# SCH_Endurance_drone_1.net
KiCad netlist of a schematic drawn in EasyEDA
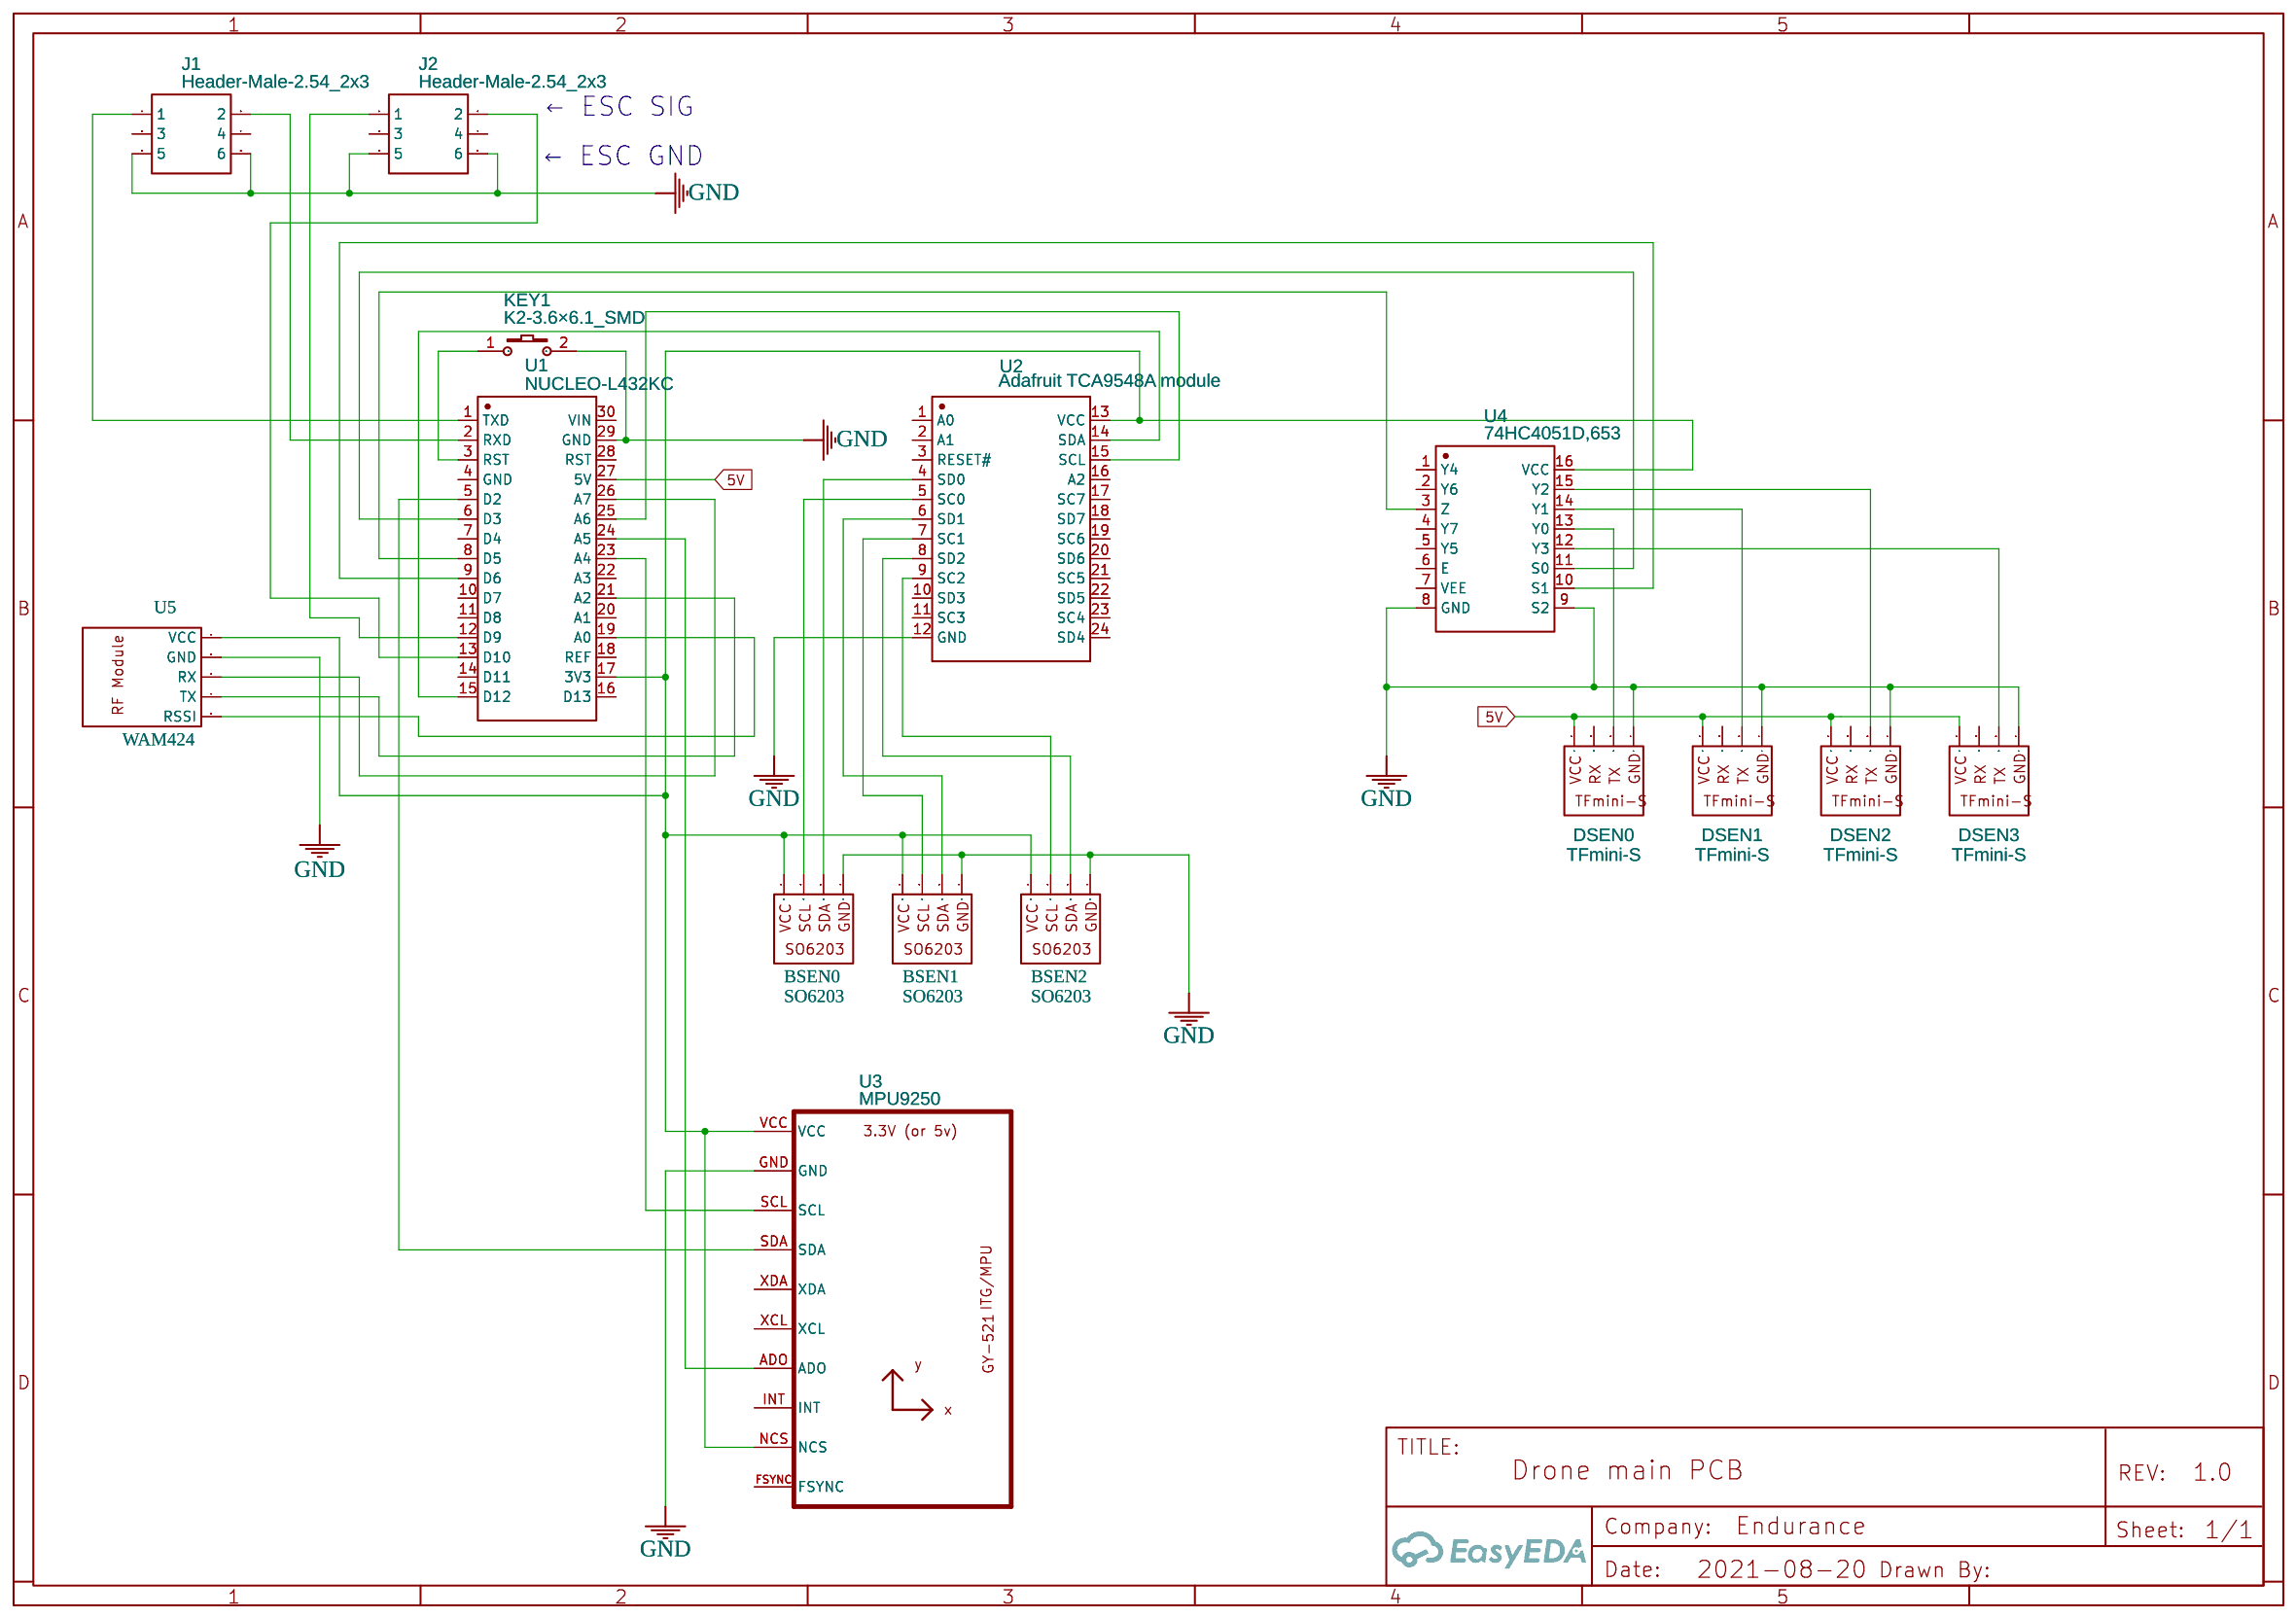
[diagram p0: schematic sheet]

(export (version "E")
  (design (tool "Eeschema 10.0.6"))
  (components
    (comp (ref "BSEN0") (value "SO6203") (libsource (lib "") (part "Unknown_405_-355")))
    (comp (ref "BSEN1") (value "SO6203") (libsource (lib "") (part "Unknown_465_-355")))
    (comp (ref "BSEN2") (value "SO6203") (libsource (lib "") (part "Unknown_530_-355")))
    (comp (ref "DSEN0") (value "TFmini-S") (libsource (lib "") (part "Unknown_805_-430")))
    (comp (ref "DSEN1") (value "TFmini-S") (libsource (lib "") (part "Unknown_870_-430")))
    (comp (ref "DSEN2") (value "TFmini-S") (libsource (lib "") (part "Unknown_935_-430")))
    (comp (ref "DSEN3") (value "TFmini-S") (libsource (lib "") (part "Unknown_1000_-430")))
    (comp (ref "J1")
      (value "Header-Male-2.54_2x3")
      (fields (field (name "BOM_Supplier Part") "C65114"))
      (libsource (lib "") (part "Header-Male-2.54_2x3"))
    )
    (comp (ref "J2")
      (value "Header-Male-2.54_2x3")
      (fields (field (name "BOM_Supplier Part") "C65114"))
      (libsource (lib "") (part "Header-Male-2.54_2x3"))
    )
    (comp (ref "KEY1")
      (value "K2-3.6×6.1_SMD")
      (fields
        (field (name "BOM_Manufacturer Part") "K2-1107ST-A4SW-06")
        (field (name "BOM_Supplier Part") "C118141")
      )
      (libsource (lib "") (part "K2-3.6×6.1_SMD"))
    )
    (comp (ref "SEN0") (value "SO6203") (libsource (lib "") (part "Unknown_410_-340")))
    (comp (ref "SEN1") (value "SO6203") (libsource (lib "") (part "Unknown_470_-340")))
    (comp (ref "SEN2") (value "SO6203") (libsource (lib "") (part "Unknown_535_-340")))
    (comp (ref "SEN3") (value "TFmini-S") (libsource (lib "") (part "Unknown_810_-415")))
    (comp (ref "SEN4") (value "TFmini-S") (libsource (lib "") (part "Unknown_875_-415")))
    (comp (ref "SEN5") (value "TFmini-S") (libsource (lib "") (part "Unknown_940_-415")))
    (comp (ref "SEN6") (value "TFmini-S") (libsource (lib "") (part "Unknown_1005_-415")))
    (comp (ref "U1")
      (value "NUCLEO-L432KC")
      (fields (field (name "BOM_Supplier Part") "C94814"))
      (libsource (lib "") (part "NUCLEO-L432KC"))
    )
    (comp (ref "U2")
      (value "Adafruit TCA9548A module")
      (fields
        (field (name "BOM_Manufacturer Part") "TCA9548APWR")
        (field (name "BOM_Supplier Part") "C130026")
      )
      (libsource (lib "") (part "TCA9548APWR"))
    )
    (comp (ref "U3") (value "MPU9250") (libsource (lib "") (part "MPU9250")))
    (comp (ref "U4")
      (value "74HC4051D,653")
      (fields (field (name "BOM_Supplier Part") "C9386"))
      (libsource (lib "") (part "74HC4051D,653"))
    )
    (comp (ref "U5") (value "WAM424") (libsource (lib "") (part "Unknown_70_-470")))
  )
  (nets
    (net (code "1") (name "5V") (class "Default")
      (node (ref "DSEN0") (pin "1") (pinfunction "1_1") (pintype "unspecified"))
      (node (ref "DSEN1") (pin "1") (pinfunction "1_1") (pintype "unspecified"))
      (node (ref "DSEN2") (pin "1") (pinfunction "1_1") (pintype "unspecified"))
      (node (ref "DSEN3") (pin "1") (pinfunction "1_1") (pintype "unspecified"))
      (node (ref "U1") (pin "27") (pinfunction "5V_27") (pintype "unspecified"))
    )
    (net (code "2") (name "GND") (class "Default")
      (node (ref "BSEN0") (pin "4") (pinfunction "4_4") (pintype "unspecified"))
      (node (ref "BSEN1") (pin "4") (pinfunction "4_4") (pintype "unspecified"))
      (node (ref "BSEN2") (pin "4") (pinfunction "4_4") (pintype "unspecified"))
      (node (ref "DSEN0") (pin "4") (pinfunction "4_4") (pintype "unspecified"))
      (node (ref "DSEN1") (pin "4") (pinfunction "4_4") (pintype "unspecified"))
      (node (ref "DSEN2") (pin "4") (pinfunction "4_4") (pintype "unspecified"))
      (node (ref "DSEN3") (pin "4") (pinfunction "4_4") (pintype "unspecified"))
      (node (ref "J1") (pin "5") (pinfunction "5_5") (pintype "input"))
      (node (ref "J1") (pin "6") (pinfunction "6_6") (pintype "input"))
      (node (ref "J2") (pin "5") (pinfunction "5_5") (pintype "input"))
      (node (ref "J2") (pin "6") (pinfunction "6_6") (pintype "input"))
      (node (ref "KEY1") (pin "2") (pinfunction "2_2") (pintype "unspecified"))
      (node (ref "U1") (pin "29") (pinfunction "GND_29") (pintype "unspecified"))
      (node (ref "U2") (pin "12") (pinfunction "GND_12") (pintype "unspecified"))
      (node (ref "U3") (pin "GND") (pinfunction "GND_GND") (pintype "bidirectional"))
      (node (ref "U4") (pin "8") (pinfunction "GND_8") (pintype "unspecified"))
      (node (ref "U4") (pin "9") (pinfunction "S2_9") (pintype "unspecified"))
      (node (ref "U5") (pin "2") (pinfunction "GND_2") (pintype "unspecified"))
    )
    (net (code "3") (name "Net-(KEY1-Pad1)") (class "Default")
      (node (ref "KEY1") (pin "1") (pinfunction "1_1") (pintype "unspecified"))
      (node (ref "U1") (pin "3") (pinfunction "RST_3") (pintype "unspecified"))
    )
    (net (code "4") (name "Net-(U1-3V3)") (class "Default")
      (node (ref "BSEN0") (pin "1") (pinfunction "1_1") (pintype "unspecified"))
      (node (ref "BSEN1") (pin "1") (pinfunction "1_1") (pintype "unspecified"))
      (node (ref "BSEN2") (pin "1") (pinfunction "1_1") (pintype "unspecified"))
      (node (ref "U1") (pin "17") (pinfunction "3V3_17") (pintype "unspecified"))
      (node (ref "U2") (pin "13") (pinfunction "VCC_13") (pintype "unspecified"))
      (node (ref "U3") (pin "NCS") (pinfunction "NCS_NCS") (pintype "bidirectional"))
      (node (ref "U3") (pin "VCC") (pinfunction "VCC_VCC") (pintype "bidirectional"))
      (node (ref "U4") (pin "16") (pinfunction "VCC_16") (pintype "unspecified"))
      (node (ref "U5") (pin "1") (pinfunction "VCC_1") (pintype "unspecified"))
    )
    (net (code "5") (name "Net-(U1-A0)") (class "Default")
      (node (ref "U1") (pin "19") (pinfunction "A0_19") (pintype "unspecified"))
      (node (ref "U5") (pin "5") (pinfunction "RSSI_5") (pintype "unspecified"))
    )
    (net (code "6") (name "Net-(U1-A2)") (class "Default")
      (node (ref "U1") (pin "21") (pinfunction "A2_21") (pintype "unspecified"))
      (node (ref "U5") (pin "4") (pinfunction "TX_4") (pintype "unspecified"))
    )
    (net (code "7") (name "Net-(U1-A4)") (class "Default")
      (node (ref "U1") (pin "23") (pinfunction "A4_23") (pintype "unspecified"))
      (node (ref "U3") (pin "SCL") (pinfunction "SCL_SCL") (pintype "bidirectional"))
    )
    (net (code "8") (name "Net-(U1-A5)") (class "Default")
      (node (ref "U1") (pin "24") (pinfunction "A5_24") (pintype "unspecified"))
      (node (ref "U3") (pin "ADO") (pinfunction "ADO_ADO") (pintype "bidirectional"))
    )
    (net (code "9") (name "Net-(U1-A6)") (class "Default")
      (node (ref "U1") (pin "25") (pinfunction "A6_25") (pintype "unspecified"))
      (node (ref "U2") (pin "15") (pinfunction "SCL_15") (pintype "unspecified"))
    )
    (net (code "10") (name "Net-(U1-A7)") (class "Default")
      (node (ref "U1") (pin "26") (pinfunction "A7_26") (pintype "unspecified"))
      (node (ref "U5") (pin "3") (pinfunction "RX_3") (pintype "unspecified"))
    )
    (net (code "11") (name "Net-(U1-D2)") (class "Default")
      (node (ref "U1") (pin "5") (pinfunction "D2_5") (pintype "unspecified"))
      (node (ref "U3") (pin "SDA") (pinfunction "SDA_SDA") (pintype "bidirectional"))
    )
    (net (code "12") (name "Net-(U1-D3)") (class "Default")
      (node (ref "U1") (pin "6") (pinfunction "D3_6") (pintype "unspecified"))
      (node (ref "U4") (pin "11") (pinfunction "S0_11") (pintype "unspecified"))
    )
    (net (code "13") (name "Net-(U1-D5)") (class "Default")
      (node (ref "U1") (pin "8") (pinfunction "D5_8") (pintype "unspecified"))
      (node (ref "U4") (pin "3") (pinfunction "Z_3") (pintype "unspecified"))
    )
    (net (code "14") (name "Net-(U1-D6)") (class "Default")
      (node (ref "U1") (pin "9") (pinfunction "D6_9") (pintype "unspecified"))
      (node (ref "U4") (pin "10") (pinfunction "S1_10") (pintype "unspecified"))
    )
    (net (code "15") (name "Net-(U1-D9)") (class "Default")
      (node (ref "J2") (pin "1") (pinfunction "1_1") (pintype "input"))
      (node (ref "U1") (pin "12") (pinfunction "D9_12") (pintype "unspecified"))
    )
    (net (code "16") (name "Net-(U1-D10)") (class "Default")
      (node (ref "J2") (pin "2") (pinfunction "2_2") (pintype "input"))
      (node (ref "U1") (pin "13") (pinfunction "D10_13") (pintype "unspecified"))
    )
    (net (code "17") (name "Net-(U1-D12)") (class "Default")
      (node (ref "U1") (pin "15") (pinfunction "D12_15") (pintype "unspecified"))
      (node (ref "U2") (pin "14") (pinfunction "SDA_14") (pintype "unspecified"))
    )
    (net (code "18") (name "Net-(U1-RXD)") (class "Default")
      (node (ref "J1") (pin "2") (pinfunction "2_2") (pintype "input"))
      (node (ref "U1") (pin "2") (pinfunction "RXD_2") (pintype "unspecified"))
    )
    (net (code "19") (name "Net-(U1-TXD)") (class "Default")
      (node (ref "J1") (pin "1") (pinfunction "1_1") (pintype "input"))
      (node (ref "U1") (pin "1") (pinfunction "TXD_1") (pintype "unspecified"))
    )
    (net (code "20") (name "Net-(U2-SC0)") (class "Default")
      (node (ref "BSEN0") (pin "2") (pinfunction "2_2") (pintype "unspecified"))
      (node (ref "U2") (pin "5") (pinfunction "SC0_5") (pintype "unspecified"))
    )
    (net (code "21") (name "Net-(U2-SC1)") (class "Default")
      (node (ref "BSEN1") (pin "2") (pinfunction "2_2") (pintype "unspecified"))
      (node (ref "U2") (pin "7") (pinfunction "SC1_7") (pintype "unspecified"))
    )
    (net (code "22") (name "Net-(U2-SC2)") (class "Default")
      (node (ref "BSEN2") (pin "2") (pinfunction "2_2") (pintype "unspecified"))
      (node (ref "U2") (pin "9") (pinfunction "SC2_9") (pintype "unspecified"))
    )
    (net (code "23") (name "Net-(U2-SD0)") (class "Default")
      (node (ref "BSEN0") (pin "3") (pinfunction "3_3") (pintype "unspecified"))
      (node (ref "U2") (pin "4") (pinfunction "SD0_4") (pintype "unspecified"))
    )
    (net (code "24") (name "Net-(U2-SD1)") (class "Default")
      (node (ref "BSEN1") (pin "3") (pinfunction "3_3") (pintype "unspecified"))
      (node (ref "U2") (pin "6") (pinfunction "SD1_6") (pintype "unspecified"))
    )
    (net (code "25") (name "Net-(U2-SD2)") (class "Default")
      (node (ref "BSEN2") (pin "3") (pinfunction "3_3") (pintype "unspecified"))
      (node (ref "U2") (pin "8") (pinfunction "SD2_8") (pintype "unspecified"))
    )
    (net (code "26") (name "Net-(U4-Y0)") (class "Default")
      (node (ref "DSEN0") (pin "3") (pinfunction "3_3") (pintype "unspecified"))
      (node (ref "U4") (pin "13") (pinfunction "Y0_13") (pintype "unspecified"))
    )
    (net (code "27") (name "Net-(U4-Y1)") (class "Default")
      (node (ref "DSEN1") (pin "3") (pinfunction "3_3") (pintype "unspecified"))
      (node (ref "U4") (pin "14") (pinfunction "Y1_14") (pintype "unspecified"))
    )
    (net (code "28") (name "Net-(U4-Y2)") (class "Default")
      (node (ref "DSEN2") (pin "3") (pinfunction "3_3") (pintype "unspecified"))
      (node (ref "U4") (pin "15") (pinfunction "Y2_15") (pintype "unspecified"))
    )
    (net (code "29") (name "Net-(U4-Y3)") (class "Default")
      (node (ref "DSEN3") (pin "3") (pinfunction "3_3") (pintype "unspecified"))
      (node (ref "U4") (pin "12") (pinfunction "Y3_12") (pintype "unspecified"))
    )
    (net (code "30") (name "unconnected-(DSEN0-Pad2)") (class "Default")
      (node (ref "DSEN0") (pin "2") (pinfunction "2_2") (pintype "unspecified"))
    )
    (net (code "31") (name "unconnected-(DSEN1-Pad2)") (class "Default")
      (node (ref "DSEN1") (pin "2") (pinfunction "2_2") (pintype "unspecified"))
    )
    (net (code "32") (name "unconnected-(DSEN2-Pad2)") (class "Default")
      (node (ref "DSEN2") (pin "2") (pinfunction "2_2") (pintype "unspecified"))
    )
    (net (code "33") (name "unconnected-(DSEN3-Pad2)") (class "Default")
      (node (ref "DSEN3") (pin "2") (pinfunction "2_2") (pintype "unspecified"))
    )
    (net (code "34") (name "unconnected-(J1-Pad3)") (class "Default")
      (node (ref "J1") (pin "3") (pinfunction "3_3") (pintype "input"))
    )
    (net (code "35") (name "unconnected-(J1-Pad4)") (class "Default")
      (node (ref "J1") (pin "4") (pinfunction "4_4") (pintype "input"))
    )
    (net (code "36") (name "unconnected-(J2-Pad3)") (class "Default")
      (node (ref "J2") (pin "3") (pinfunction "3_3") (pintype "input"))
    )
    (net (code "37") (name "unconnected-(J2-Pad4)") (class "Default")
      (node (ref "J2") (pin "4") (pinfunction "4_4") (pintype "input"))
    )
    (net (code "38") (name "unconnected-(U1-A1-Pad20)") (class "Default")
      (node (ref "U1") (pin "20") (pinfunction "A1_20") (pintype "unspecified"))
    )
    (net (code "39") (name "unconnected-(U1-A3-Pad22)") (class "Default")
      (node (ref "U1") (pin "22") (pinfunction "A3_22") (pintype "unspecified"))
    )
    (net (code "40") (name "unconnected-(U1-D4-Pad7)") (class "Default")
      (node (ref "U1") (pin "7") (pinfunction "D4_7") (pintype "unspecified"))
    )
    (net (code "41") (name "unconnected-(U1-D7-Pad10)") (class "Default")
      (node (ref "U1") (pin "10") (pinfunction "D7_10") (pintype "unspecified"))
    )
    (net (code "42") (name "unconnected-(U1-D8-Pad11)") (class "Default")
      (node (ref "U1") (pin "11") (pinfunction "D8_11") (pintype "unspecified"))
    )
    (net (code "43") (name "unconnected-(U1-D11-Pad14)") (class "Default")
      (node (ref "U1") (pin "14") (pinfunction "D11_14") (pintype "unspecified"))
    )
    (net (code "44") (name "unconnected-(U1-D13-Pad16)") (class "Default")
      (node (ref "U1") (pin "16") (pinfunction "D13_16") (pintype "unspecified"))
    )
    (net (code "45") (name "unconnected-(U1-GND-Pad4)") (class "Default")
      (node (ref "U1") (pin "4") (pinfunction "GND_4") (pintype "unspecified"))
    )
    (net (code "46") (name "unconnected-(U1-REF-Pad18)") (class "Default")
      (node (ref "U1") (pin "18") (pinfunction "REF_18") (pintype "unspecified"))
    )
    (net (code "47") (name "unconnected-(U1-RST-Pad28)") (class "Default")
      (node (ref "U1") (pin "28") (pinfunction "RST_28") (pintype "unspecified"))
    )
    (net (code "48") (name "unconnected-(U1-VIN-Pad30)") (class "Default")
      (node (ref "U1") (pin "30") (pinfunction "VIN_30") (pintype "unspecified"))
    )
    (net (code "49") (name "unconnected-(U2-A0-Pad1)") (class "Default")
      (node (ref "U2") (pin "1") (pinfunction "A0_1") (pintype "unspecified"))
    )
    (net (code "50") (name "unconnected-(U2-A1-Pad2)") (class "Default")
      (node (ref "U2") (pin "2") (pinfunction "A1_2") (pintype "unspecified"))
    )
    (net (code "51") (name "unconnected-(U2-A2-Pad16)") (class "Default")
      (node (ref "U2") (pin "16") (pinfunction "A2_16") (pintype "unspecified"))
    )
    (net (code "52") (name "unconnected-(U2-RESET#-Pad3)") (class "Default")
      (node (ref "U2") (pin "3") (pinfunction "RESET#_3") (pintype "unspecified"))
    )
    (net (code "53") (name "unconnected-(U2-SC3-Pad11)") (class "Default")
      (node (ref "U2") (pin "11") (pinfunction "SC3_11") (pintype "unspecified"))
    )
    (net (code "54") (name "unconnected-(U2-SC4-Pad23)") (class "Default")
      (node (ref "U2") (pin "23") (pinfunction "SC4_23") (pintype "unspecified"))
    )
    (net (code "55") (name "unconnected-(U2-SC5-Pad21)") (class "Default")
      (node (ref "U2") (pin "21") (pinfunction "SC5_21") (pintype "unspecified"))
    )
    (net (code "56") (name "unconnected-(U2-SC6-Pad19)") (class "Default")
      (node (ref "U2") (pin "19") (pinfunction "SC6_19") (pintype "unspecified"))
    )
    (net (code "57") (name "unconnected-(U2-SC7-Pad17)") (class "Default")
      (node (ref "U2") (pin "17") (pinfunction "SC7_17") (pintype "unspecified"))
    )
    (net (code "58") (name "unconnected-(U2-SD3-Pad10)") (class "Default")
      (node (ref "U2") (pin "10") (pinfunction "SD3_10") (pintype "unspecified"))
    )
    (net (code "59") (name "unconnected-(U2-SD4-Pad24)") (class "Default")
      (node (ref "U2") (pin "24") (pinfunction "SD4_24") (pintype "unspecified"))
    )
    (net (code "60") (name "unconnected-(U2-SD5-Pad22)") (class "Default")
      (node (ref "U2") (pin "22") (pinfunction "SD5_22") (pintype "unspecified"))
    )
    (net (code "61") (name "unconnected-(U2-SD6-Pad20)") (class "Default")
      (node (ref "U2") (pin "20") (pinfunction "SD6_20") (pintype "unspecified"))
    )
    (net (code "62") (name "unconnected-(U2-SD7-Pad18)") (class "Default")
      (node (ref "U2") (pin "18") (pinfunction "SD7_18") (pintype "unspecified"))
    )
    (net (code "63") (name "unconnected-(U3-PadFSYNC)") (class "Default")
      (node (ref "U3") (pin "FSYNC") (pinfunction "FSYNC_FSYNC") (pintype "bidirectional"))
    )
    (net (code "64") (name "unconnected-(U3-PadINT)") (class "Default")
      (node (ref "U3") (pin "INT") (pinfunction "INT_INT") (pintype "bidirectional"))
    )
    (net (code "65") (name "unconnected-(U3-PadXCL)") (class "Default")
      (node (ref "U3") (pin "XCL") (pinfunction "XCL_XCL") (pintype "bidirectional"))
    )
    (net (code "66") (name "unconnected-(U3-PadXDA)") (class "Default")
      (node (ref "U3") (pin "XDA") (pinfunction "XDA_XDA") (pintype "bidirectional"))
    )
    (net (code "67") (name "unconnected-(U4-E-Pad6)") (class "Default")
      (node (ref "U4") (pin "6") (pinfunction "E_6") (pintype "unspecified"))
    )
    (net (code "68") (name "unconnected-(U4-VEE-Pad7)") (class "Default")
      (node (ref "U4") (pin "7") (pinfunction "VEE_7") (pintype "unspecified"))
    )
    (net (code "69") (name "unconnected-(U4-Y4-Pad1)") (class "Default")
      (node (ref "U4") (pin "1") (pinfunction "Y4_1") (pintype "unspecified"))
    )
    (net (code "70") (name "unconnected-(U4-Y5-Pad5)") (class "Default")
      (node (ref "U4") (pin "5") (pinfunction "Y5_5") (pintype "unspecified"))
    )
    (net (code "71") (name "unconnected-(U4-Y6-Pad2)") (class "Default")
      (node (ref "U4") (pin "2") (pinfunction "Y6_2") (pintype "unspecified"))
    )
    (net (code "72") (name "unconnected-(U4-Y7-Pad4)") (class "Default")
      (node (ref "U4") (pin "4") (pinfunction "Y7_4") (pintype "unspecified"))
    )
  )
)
